# sensor.net
KiCad netlist of a schematic drawn in Altium Designer
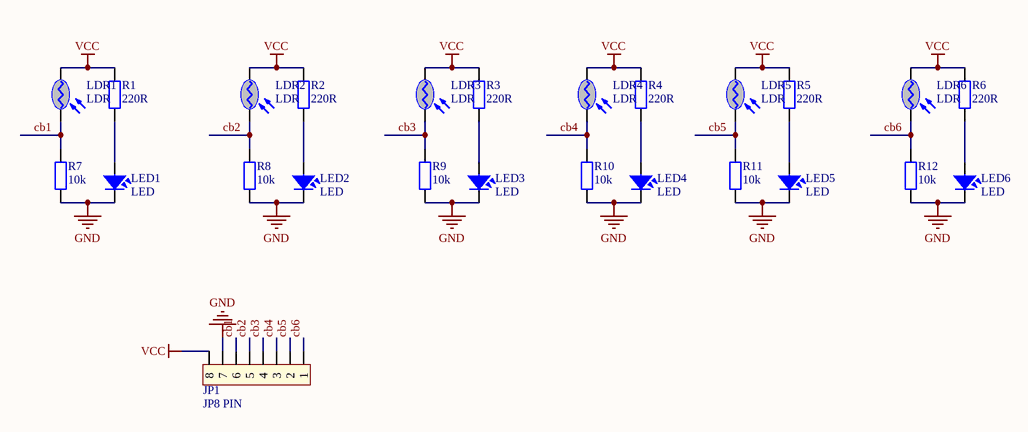
[diagram p0: sensor.SchDoc]

(export (version "E")
  (design (tool "Eeschema 10.0.6"))
  (components
    (comp (ref "JP1") (value "JP8 PIN") (footprint "JP8") (libsource (lib "syhaunguyen") (part "JP8")))
    (comp (ref "LDR1")
      (value "LDR")
      (footprint "LED-5 GRe")
      (description "Quang Tro")
      (libsource (lib "syhaunguyen") (part "LDR"))
    )
    (comp (ref "LDR2")
      (value "LDR")
      (footprint "LED-5 GRe")
      (description "Quang Tro")
      (libsource (lib "syhaunguyen") (part "LDR"))
    )
    (comp (ref "LDR3")
      (value "LDR")
      (footprint "LED-5 GRe")
      (description "Quang Tro")
      (libsource (lib "syhaunguyen") (part "LDR"))
    )
    (comp (ref "LDR4")
      (value "LDR")
      (footprint "LED-5 GRe")
      (description "Quang Tro")
      (libsource (lib "syhaunguyen") (part "LDR"))
    )
    (comp (ref "LDR5")
      (value "LDR")
      (footprint "LED-5 GRe")
      (description "Quang Tro")
      (libsource (lib "syhaunguyen") (part "LDR"))
    )
    (comp (ref "LDR6")
      (value "LDR")
      (footprint "LED-5 GRe")
      (description "Quang Tro")
      (libsource (lib "syhaunguyen") (part "LDR"))
    )
    (comp (ref "LED1")
      (value "LED")
      (footprint "LED-5TRED")
      (description "Led  Vuong")
      (libsource (lib "syhaunguyen") (part "LED"))
    )
    (comp (ref "LED2")
      (value "LED")
      (footprint "LED-5TRED")
      (description "Led  Vuong")
      (libsource (lib "syhaunguyen") (part "LED"))
    )
    (comp (ref "LED3")
      (value "LED")
      (footprint "LED-5TRED")
      (description "Led  Vuong")
      (libsource (lib "syhaunguyen") (part "LED"))
    )
    (comp (ref "LED4")
      (value "LED")
      (footprint "LED-5TRED")
      (description "Led  Vuong")
      (libsource (lib "syhaunguyen") (part "LED"))
    )
    (comp (ref "LED5")
      (value "LED")
      (footprint "LED-5TRED")
      (description "Led  Vuong")
      (libsource (lib "syhaunguyen") (part "LED"))
    )
    (comp (ref "LED6")
      (value "LED")
      (footprint "LED-5TRED")
      (description "Led  Vuong")
      (libsource (lib "syhaunguyen") (part "LED"))
    )
    (comp (ref "R1")
      (value "220R")
      (footprint "R1/4W")
      (description "Resistor 1/4W")
      (libsource (lib "syhaunguyen") (part "R1/4W"))
    )
    (comp (ref "R2")
      (value "220R")
      (footprint "R1/4W")
      (description "Resistor 1/4W")
      (libsource (lib "syhaunguyen") (part "R1/4W"))
    )
    (comp (ref "R3")
      (value "220R")
      (footprint "R1/4W")
      (description "Resistor 1/4W")
      (libsource (lib "syhaunguyen") (part "R1/4W"))
    )
    (comp (ref "R4")
      (value "220R")
      (footprint "R1/4W")
      (description "Resistor 1/4W")
      (libsource (lib "syhaunguyen") (part "R1/4W"))
    )
    (comp (ref "R5")
      (value "220R")
      (footprint "R1/4W")
      (description "Resistor 1/4W")
      (libsource (lib "syhaunguyen") (part "R1/4W"))
    )
    (comp (ref "R6")
      (value "220R")
      (footprint "R1/4W")
      (description "Resistor 1/4W")
      (libsource (lib "syhaunguyen") (part "R1/4W"))
    )
    (comp (ref "R7")
      (value "10k")
      (footprint "R1/4W")
      (description "Resistor 1/4W")
      (libsource (lib "syhaunguyen") (part "R1/4W"))
    )
    (comp (ref "R8")
      (value "10k")
      (footprint "R1/4W")
      (description "Resistor 1/4W")
      (libsource (lib "syhaunguyen") (part "R1/4W"))
    )
    (comp (ref "R9")
      (value "10k")
      (footprint "R1/4W")
      (description "Resistor 1/4W")
      (libsource (lib "syhaunguyen") (part "R1/4W"))
    )
    (comp (ref "R10")
      (value "10k")
      (footprint "R1/4W")
      (description "Resistor 1/4W")
      (libsource (lib "syhaunguyen") (part "R1/4W"))
    )
    (comp (ref "R11")
      (value "10k")
      (footprint "R1/4W")
      (description "Resistor 1/4W")
      (libsource (lib "syhaunguyen") (part "R1/4W"))
    )
    (comp (ref "R12")
      (value "10k")
      (footprint "R1/4W")
      (description "Resistor 1/4W")
      (libsource (lib "syhaunguyen") (part "R1/4W"))
    )
  )
  (nets
    (net (code "1") (name "/cb1") (class "Default")
      (node (ref "JP1") (pin "6") (pinfunction "6_6") (pintype "passive"))
      (node (ref "LDR1") (pin "2") (pinfunction "K_2") (pintype "passive"))
      (node (ref "R7") (pin "1") (pinfunction "1_1") (pintype "passive"))
    )
    (net (code "2") (name "/cb2") (class "Default")
      (node (ref "JP1") (pin "5") (pinfunction "5_5") (pintype "passive"))
      (node (ref "LDR2") (pin "2") (pinfunction "K_2") (pintype "passive"))
      (node (ref "R8") (pin "1") (pinfunction "1_1") (pintype "passive"))
    )
    (net (code "3") (name "/cb3") (class "Default")
      (node (ref "JP1") (pin "4") (pinfunction "4_4") (pintype "passive"))
      (node (ref "LDR3") (pin "2") (pinfunction "K_2") (pintype "passive"))
      (node (ref "R9") (pin "1") (pinfunction "1_1") (pintype "passive"))
    )
    (net (code "4") (name "/cb4") (class "Default")
      (node (ref "JP1") (pin "3") (pinfunction "3_3") (pintype "passive"))
      (node (ref "LDR4") (pin "2") (pinfunction "K_2") (pintype "passive"))
      (node (ref "R10") (pin "1") (pinfunction "1_1") (pintype "passive"))
    )
    (net (code "5") (name "/cb5") (class "Default")
      (node (ref "JP1") (pin "2") (pinfunction "2_2") (pintype "passive"))
      (node (ref "LDR5") (pin "2") (pinfunction "K_2") (pintype "passive"))
      (node (ref "R11") (pin "1") (pinfunction "1_1") (pintype "passive"))
    )
    (net (code "6") (name "/cb6") (class "Default")
      (node (ref "JP1") (pin "1") (pinfunction "1_1") (pintype "passive"))
      (node (ref "LDR6") (pin "2") (pinfunction "K_2") (pintype "passive"))
      (node (ref "R12") (pin "1") (pinfunction "1_1") (pintype "passive"))
    )
    (net (code "7") (name "GND") (class "Default")
      (node (ref "JP1") (pin "7") (pinfunction "7_7") (pintype "passive"))
      (node (ref "LED1") (pin "2") (pinfunction "2_2") (pintype "passive"))
      (node (ref "LED2") (pin "2") (pinfunction "2_2") (pintype "passive"))
      (node (ref "LED3") (pin "2") (pinfunction "2_2") (pintype "passive"))
      (node (ref "LED4") (pin "2") (pinfunction "2_2") (pintype "passive"))
      (node (ref "LED5") (pin "2") (pinfunction "2_2") (pintype "passive"))
      (node (ref "LED6") (pin "2") (pinfunction "2_2") (pintype "passive"))
      (node (ref "R10") (pin "2") (pinfunction "2_2") (pintype "passive"))
      (node (ref "R11") (pin "2") (pinfunction "2_2") (pintype "passive"))
      (node (ref "R12") (pin "2") (pinfunction "2_2") (pintype "passive"))
      (node (ref "R7") (pin "2") (pinfunction "2_2") (pintype "passive"))
      (node (ref "R8") (pin "2") (pinfunction "2_2") (pintype "passive"))
      (node (ref "R9") (pin "2") (pinfunction "2_2") (pintype "passive"))
    )
    (net (code "8") (name "Net-(LED1-Pad1)") (class "Default")
      (node (ref "LED1") (pin "1") (pinfunction "1_1") (pintype "passive"))
      (node (ref "R1") (pin "2") (pinfunction "2_2") (pintype "passive"))
    )
    (net (code "9") (name "Net-(LED2-Pad1)") (class "Default")
      (node (ref "LED2") (pin "1") (pinfunction "1_1") (pintype "passive"))
      (node (ref "R2") (pin "2") (pinfunction "2_2") (pintype "passive"))
    )
    (net (code "10") (name "Net-(LED3-Pad1)") (class "Default")
      (node (ref "LED3") (pin "1") (pinfunction "1_1") (pintype "passive"))
      (node (ref "R3") (pin "2") (pinfunction "2_2") (pintype "passive"))
    )
    (net (code "11") (name "Net-(LED4-Pad1)") (class "Default")
      (node (ref "LED4") (pin "1") (pinfunction "1_1") (pintype "passive"))
      (node (ref "R4") (pin "2") (pinfunction "2_2") (pintype "passive"))
    )
    (net (code "12") (name "Net-(LED5-Pad1)") (class "Default")
      (node (ref "LED5") (pin "1") (pinfunction "1_1") (pintype "passive"))
      (node (ref "R5") (pin "2") (pinfunction "2_2") (pintype "passive"))
    )
    (net (code "13") (name "Net-(LED6-Pad1)") (class "Default")
      (node (ref "LED6") (pin "1") (pinfunction "1_1") (pintype "passive"))
      (node (ref "R6") (pin "2") (pinfunction "2_2") (pintype "passive"))
    )
    (net (code "14") (name "VCC") (class "Default")
      (node (ref "JP1") (pin "8") (pinfunction "8_8") (pintype "passive"))
      (node (ref "LDR1") (pin "1") (pinfunction "A_1") (pintype "passive"))
      (node (ref "LDR2") (pin "1") (pinfunction "A_1") (pintype "passive"))
      (node (ref "LDR3") (pin "1") (pinfunction "A_1") (pintype "passive"))
      (node (ref "LDR4") (pin "1") (pinfunction "A_1") (pintype "passive"))
      (node (ref "LDR5") (pin "1") (pinfunction "A_1") (pintype "passive"))
      (node (ref "LDR6") (pin "1") (pinfunction "A_1") (pintype "passive"))
      (node (ref "R1") (pin "1") (pinfunction "1_1") (pintype "passive"))
      (node (ref "R2") (pin "1") (pinfunction "1_1") (pintype "passive"))
      (node (ref "R3") (pin "1") (pinfunction "1_1") (pintype "passive"))
      (node (ref "R4") (pin "1") (pinfunction "1_1") (pintype "passive"))
      (node (ref "R5") (pin "1") (pinfunction "1_1") (pintype "passive"))
      (node (ref "R6") (pin "1") (pinfunction "1_1") (pintype "passive"))
    )
  )
)
